# 1LFO_v2.net
KiCad netlist of a schematic drawn in EAGLE
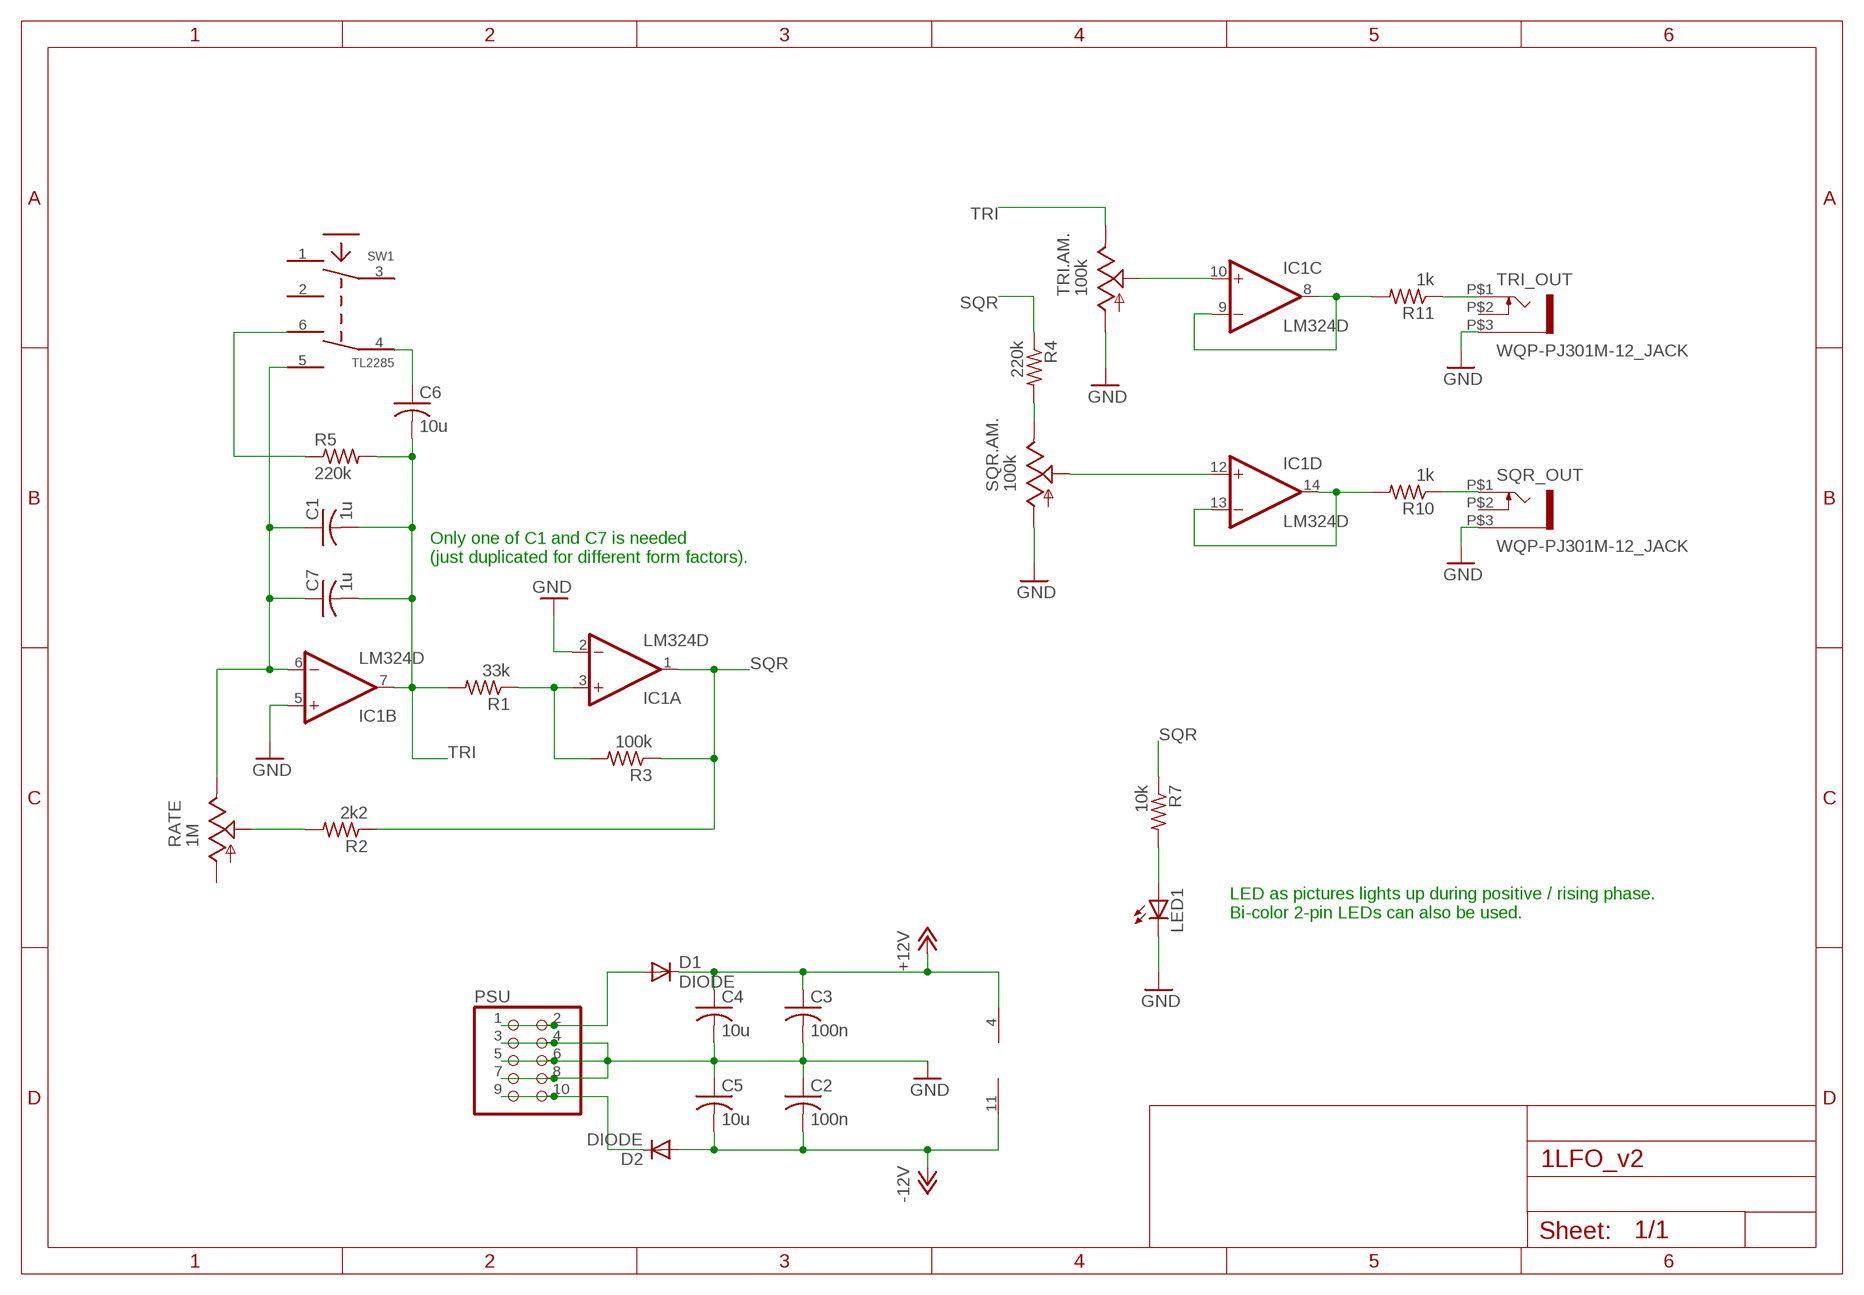
[diagram p0: schematic, sheet 1]

(export (version "E")
  (design (tool "Eeschema 10.0.6"))
  (components
    (comp (ref "C1")
      (value "1u")
      (footprint "eagle-import:C1206K")
      (libsource (lib "eagle-import") (part "C-USC1206K"))
    )
    (comp (ref "C2")
      (value "100n")
      (footprint "eagle-import:C0603K")
      (libsource (lib "eagle-import") (part "C-USC0603K"))
    )
    (comp (ref "C3")
      (value "100n")
      (footprint "eagle-import:C0603K")
      (libsource (lib "eagle-import") (part "C-USC0603K"))
    )
    (comp (ref "C4")
      (value "10u")
      (footprint "eagle-import:C1206K")
      (libsource (lib "eagle-import") (part "C-USC1206K"))
    )
    (comp (ref "C5")
      (value "10u")
      (footprint "eagle-import:C1206K")
      (libsource (lib "eagle-import") (part "C-USC1206K"))
    )
    (comp (ref "C6")
      (value "10u")
      (footprint "eagle-import:C1206K")
      (libsource (lib "eagle-import") (part "C-USC1206K"))
    )
    (comp (ref "C7")
      (value "1u")
      (footprint "eagle-import:C0603K")
      (libsource (lib "eagle-import") (part "C-USC0603K"))
    )
    (comp (ref "D1")
      (value "DIODE")
      (footprint "eagle-import:DO214AA")
      (libsource (lib "eagle-import") (part "DIODE-DO214AA"))
    )
    (comp (ref "D2")
      (value "DIODE")
      (footprint "eagle-import:DO214AA")
      (libsource (lib "eagle-import") (part "DIODE-DO214AA"))
    )
    (comp (ref "IC1")
      (value "LM324D")
      (footprint "eagle-import:SO14")
      (libsource (lib "eagle-import") (part "LM324D"))
    )
    (comp (ref "LED1")
      (value "LED5MM")
      (footprint "eagle-import:LED5MM")
      (libsource (lib "eagle-import") (part "LED5MM"))
    )
    (comp (ref "PSU")
      (value "PINHD-2X5")
      (footprint "eagle-import:2X05")
      (libsource (lib "eagle-import") (part "PINHD-2X5"))
    )
    (comp (ref "R1")
      (value "33k")
      (footprint "eagle-import:R0603")
      (libsource (lib "eagle-import") (part "R-US_R0603"))
    )
    (comp (ref "R2")
      (value "2k2")
      (footprint "eagle-import:R0603")
      (libsource (lib "eagle-import") (part "R-US_R0603"))
    )
    (comp (ref "R3")
      (value "100k")
      (footprint "eagle-import:R0603")
      (libsource (lib "eagle-import") (part "R-US_R0603"))
    )
    (comp (ref "R4")
      (value "220k")
      (footprint "eagle-import:R0603")
      (libsource (lib "eagle-import") (part "R-US_R0603"))
    )
    (comp (ref "R5")
      (value "220k")
      (footprint "eagle-import:R0603")
      (libsource (lib "eagle-import") (part "R-US_R0603"))
    )
    (comp (ref "R7")
      (value "10k")
      (footprint "eagle-import:R0603")
      (libsource (lib "eagle-import") (part "R-US_R0603"))
    )
    (comp (ref "R10")
      (value "1k")
      (footprint "eagle-import:R0603")
      (libsource (lib "eagle-import") (part "R-US_R0603"))
    )
    (comp (ref "R11")
      (value "1k")
      (footprint "eagle-import:R0603")
      (libsource (lib "eagle-import") (part "R-US_R0603"))
    )
    (comp (ref "RATE")
      (value "1M")
      (footprint "eagle-import:ALPS_POT_VERTICAL")
      (libsource (lib "eagle-import") (part "POT_USVERTICAL"))
    )
    (comp (ref "SQR.AM.")
      (value "100k")
      (footprint "eagle-import:ALPS_POT_VERTICAL")
      (libsource (lib "eagle-import") (part "POT_USVERTICAL"))
    )
    (comp (ref "SQR_OUT")
      (value "WQP-PJ301M-12_JACK")
      (footprint "eagle-import:WQP-PJ301M-12_JACK")
      (libsource (lib "eagle-import") (part "WQP-PJ301M-12_JACK"))
    )
    (comp (ref "SW1")
      (value "TL2285")
      (footprint "eagle-import:TL2285_PCB")
      (libsource (lib "eagle-import") (part "TL2285"))
    )
    (comp (ref "TRI.AM.")
      (value "100k")
      (footprint "eagle-import:ALPS_POT_VERTICAL")
      (libsource (lib "eagle-import") (part "POT_USVERTICAL"))
    )
    (comp (ref "TRI_OUT")
      (value "WQP-PJ301M-12_JACK")
      (footprint "eagle-import:WQP-PJ301M-12_JACK")
      (libsource (lib "eagle-import") (part "WQP-PJ301M-12_JACK"))
    )
  )
  (nets
    (net (code "1") (name "+12V") (class "Default")
      (node (ref "C3") (pin "1") (pinfunction "1_1") (pintype "passive"))
      (node (ref "C4") (pin "1") (pinfunction "1_1") (pintype "passive"))
      (node (ref "D1") (pin "C") (pinfunction "C_C") (pintype "passive"))
      (node (ref "IC1") (pin "4") (pinfunction "V+_4") (pintype "power_in"))
    )
    (net (code "2") (name "-12V") (class "Default")
      (node (ref "C2") (pin "2") (pinfunction "2_2") (pintype "passive"))
      (node (ref "C5") (pin "2") (pinfunction "2_2") (pintype "passive"))
      (node (ref "D2") (pin "A") (pinfunction "A_A") (pintype "passive"))
      (node (ref "IC1") (pin "11") (pinfunction "V-_11") (pintype "power_in"))
    )
    (net (code "3") (name "/SQR") (class "Default")
      (node (ref "IC1") (pin "1") (pinfunction "OUT_1") (pintype "output"))
      (node (ref "R2") (pin "1") (pinfunction "1_1") (pintype "passive"))
      (node (ref "R3") (pin "1") (pinfunction "1_1") (pintype "passive"))
      (node (ref "R4") (pin "1") (pinfunction "1_1") (pintype "passive"))
      (node (ref "R7") (pin "1") (pinfunction "1_1") (pintype "passive"))
    )
    (net (code "4") (name "/TRI") (class "Default")
      (node (ref "C1") (pin "2") (pinfunction "2_2") (pintype "passive"))
      (node (ref "C6") (pin "2") (pinfunction "2_2") (pintype "passive"))
      (node (ref "C7") (pin "2") (pinfunction "2_2") (pintype "passive"))
      (node (ref "IC1") (pin "7") (pinfunction "OUT_7") (pintype "output"))
      (node (ref "R1") (pin "2") (pinfunction "2_2") (pintype "passive"))
      (node (ref "R5") (pin "2") (pinfunction "2_2") (pintype "passive"))
      (node (ref "TRI.AM.") (pin "P$1") (pinfunction "E_P$1") (pintype "passive"))
    )
    (net (code "5") (name "GND") (class "Default")
      (node (ref "C2") (pin "1") (pinfunction "1_1") (pintype "passive"))
      (node (ref "C3") (pin "2") (pinfunction "2_2") (pintype "passive"))
      (node (ref "C4") (pin "2") (pinfunction "2_2") (pintype "passive"))
      (node (ref "C5") (pin "1") (pinfunction "1_1") (pintype "passive"))
      (node (ref "IC1") (pin "2") (pinfunction "-IN_2") (pintype "input"))
      (node (ref "IC1") (pin "5") (pinfunction "+IN_5") (pintype "input"))
      (node (ref "LED1") (pin "K") (pinfunction "C_K") (pintype "passive"))
      (node (ref "PSU") (pin "3") (pinfunction "3_3") (pintype "passive"))
      (node (ref "PSU") (pin "4") (pinfunction "4_4") (pintype "passive"))
      (node (ref "PSU") (pin "5") (pinfunction "5_5") (pintype "passive"))
      (node (ref "PSU") (pin "6") (pinfunction "6_6") (pintype "passive"))
      (node (ref "PSU") (pin "7") (pinfunction "7_7") (pintype "passive"))
      (node (ref "PSU") (pin "8") (pinfunction "8_8") (pintype "passive"))
      (node (ref "SQR.AM.") (pin "P$3") (pinfunction "A_P$3") (pintype "passive"))
      (node (ref "SQR_OUT") (pin "P$3") (pinfunction "1_P$3") (pintype "passive"))
      (node (ref "TRI.AM.") (pin "P$3") (pinfunction "A_P$3") (pintype "passive"))
      (node (ref "TRI_OUT") (pin "P$3") (pinfunction "1_P$3") (pintype "passive"))
    )
    (net (code "6") (name "Net-(D1-PadA)") (class "Default")
      (node (ref "D1") (pin "A") (pinfunction "A_A") (pintype "passive"))
      (node (ref "PSU") (pin "1") (pinfunction "1_1") (pintype "passive"))
      (node (ref "PSU") (pin "2") (pinfunction "2_2") (pintype "passive"))
    )
    (net (code "7") (name "Net-(D2-PadC)") (class "Default")
      (node (ref "D2") (pin "C") (pinfunction "C_C") (pintype "passive"))
      (node (ref "PSU") (pin "10") (pinfunction "10_10") (pintype "passive"))
      (node (ref "PSU") (pin "9") (pinfunction "9_9") (pintype "passive"))
    )
    (net (code "8") (name "Net-(IC1A-+IN)") (class "Default")
      (node (ref "IC1") (pin "3") (pinfunction "+IN_3") (pintype "input"))
      (node (ref "R1") (pin "1") (pinfunction "1_1") (pintype "passive"))
      (node (ref "R3") (pin "2") (pinfunction "2_2") (pintype "passive"))
    )
    (net (code "9") (name "Net-(IC1B--IN)") (class "Default")
      (node (ref "C1") (pin "1") (pinfunction "1_1") (pintype "passive"))
      (node (ref "C7") (pin "1") (pinfunction "1_1") (pintype "passive"))
      (node (ref "IC1") (pin "6") (pinfunction "-IN_6") (pintype "input"))
      (node (ref "RATE") (pin "P$1") (pinfunction "E_P$1") (pintype "passive"))
      (node (ref "SW1") (pin "5") (pinfunction "P5_5") (pintype "bidirectional"))
    )
    (net (code "10") (name "Net-(IC1C-+IN)") (class "Default")
      (node (ref "IC1") (pin "10") (pinfunction "+IN_10") (pintype "input"))
      (node (ref "TRI.AM.") (pin "P$2") (pinfunction "S_P$2") (pintype "passive"))
    )
    (net (code "11") (name "Net-(IC1C--IN)") (class "Default")
      (node (ref "IC1") (pin "8") (pinfunction "OUT_8") (pintype "output"))
      (node (ref "IC1") (pin "9") (pinfunction "-IN_9") (pintype "input"))
      (node (ref "R11") (pin "2") (pinfunction "2_2") (pintype "passive"))
    )
    (net (code "12") (name "Net-(IC1D-+IN)") (class "Default")
      (node (ref "IC1") (pin "12") (pinfunction "+IN_12") (pintype "input"))
      (node (ref "SQR.AM.") (pin "P$2") (pinfunction "S_P$2") (pintype "passive"))
    )
    (net (code "13") (name "Net-(IC1D--IN)") (class "Default")
      (node (ref "IC1") (pin "13") (pinfunction "-IN_13") (pintype "input"))
      (node (ref "IC1") (pin "14") (pinfunction "OUT_14") (pintype "output"))
      (node (ref "R10") (pin "2") (pinfunction "2_2") (pintype "passive"))
    )
    (net (code "14") (name "Net-(LED1-PadA)") (class "Default")
      (node (ref "LED1") (pin "A") (pinfunction "A_A") (pintype "passive"))
      (node (ref "R7") (pin "2") (pinfunction "2_2") (pintype "passive"))
    )
    (net (code "15") (name "Net-(RATE-S)") (class "Default")
      (node (ref "R2") (pin "2") (pinfunction "2_2") (pintype "passive"))
      (node (ref "RATE") (pin "P$2") (pinfunction "S_P$2") (pintype "passive"))
    )
    (net (code "16") (name "Net-(SQR.AM.-E)") (class "Default")
      (node (ref "R4") (pin "2") (pinfunction "2_2") (pintype "passive"))
      (node (ref "SQR.AM.") (pin "P$1") (pinfunction "E_P$1") (pintype "passive"))
    )
    (net (code "17") (name "Net-(SQR_OUT-2)") (class "Default")
      (node (ref "R10") (pin "1") (pinfunction "1_1") (pintype "passive"))
      (node (ref "SQR_OUT") (pin "P$1") (pinfunction "2_P$1") (pintype "passive"))
    )
    (net (code "18") (name "Net-(SW1-P4)") (class "Default")
      (node (ref "C6") (pin "1") (pinfunction "1_1") (pintype "passive"))
      (node (ref "SW1") (pin "4") (pinfunction "P4_4") (pintype "bidirectional"))
    )
    (net (code "19") (name "Net-(SW1-P6)") (class "Default")
      (node (ref "R5") (pin "1") (pinfunction "1_1") (pintype "passive"))
      (node (ref "SW1") (pin "6") (pinfunction "P6_6") (pintype "bidirectional"))
    )
    (net (code "20") (name "Net-(TRI_OUT-2)") (class "Default")
      (node (ref "R11") (pin "1") (pinfunction "1_1") (pintype "passive"))
      (node (ref "TRI_OUT") (pin "P$1") (pinfunction "2_P$1") (pintype "passive"))
    )
    (net (code "21") (name "unconnected-(RATE-A-PadP$3)") (class "Default")
      (node (ref "RATE") (pin "P$3") (pinfunction "A_P$3") (pintype "passive"))
    )
    (net (code "22") (name "unconnected-(SQR_OUT-3-PadP$2)") (class "Default")
      (node (ref "SQR_OUT") (pin "P$2") (pinfunction "3_P$2") (pintype "passive"))
    )
    (net (code "23") (name "unconnected-(SW1-P1-Pad1)") (class "Default")
      (node (ref "SW1") (pin "1") (pinfunction "P1_1") (pintype "bidirectional"))
    )
    (net (code "24") (name "unconnected-(SW1-P2-Pad2)") (class "Default")
      (node (ref "SW1") (pin "2") (pinfunction "P2_2") (pintype "bidirectional"))
    )
    (net (code "25") (name "unconnected-(SW1-P3-Pad3)") (class "Default")
      (node (ref "SW1") (pin "3") (pinfunction "P3_3") (pintype "bidirectional"))
    )
    (net (code "26") (name "unconnected-(TRI_OUT-3-PadP$2)") (class "Default")
      (node (ref "TRI_OUT") (pin "P$2") (pinfunction "3_P$2") (pintype "passive"))
    )
  )
)
